# VoltageSourcePCBV3.net
KiCad netlist of a schematic drawn in EAGLE
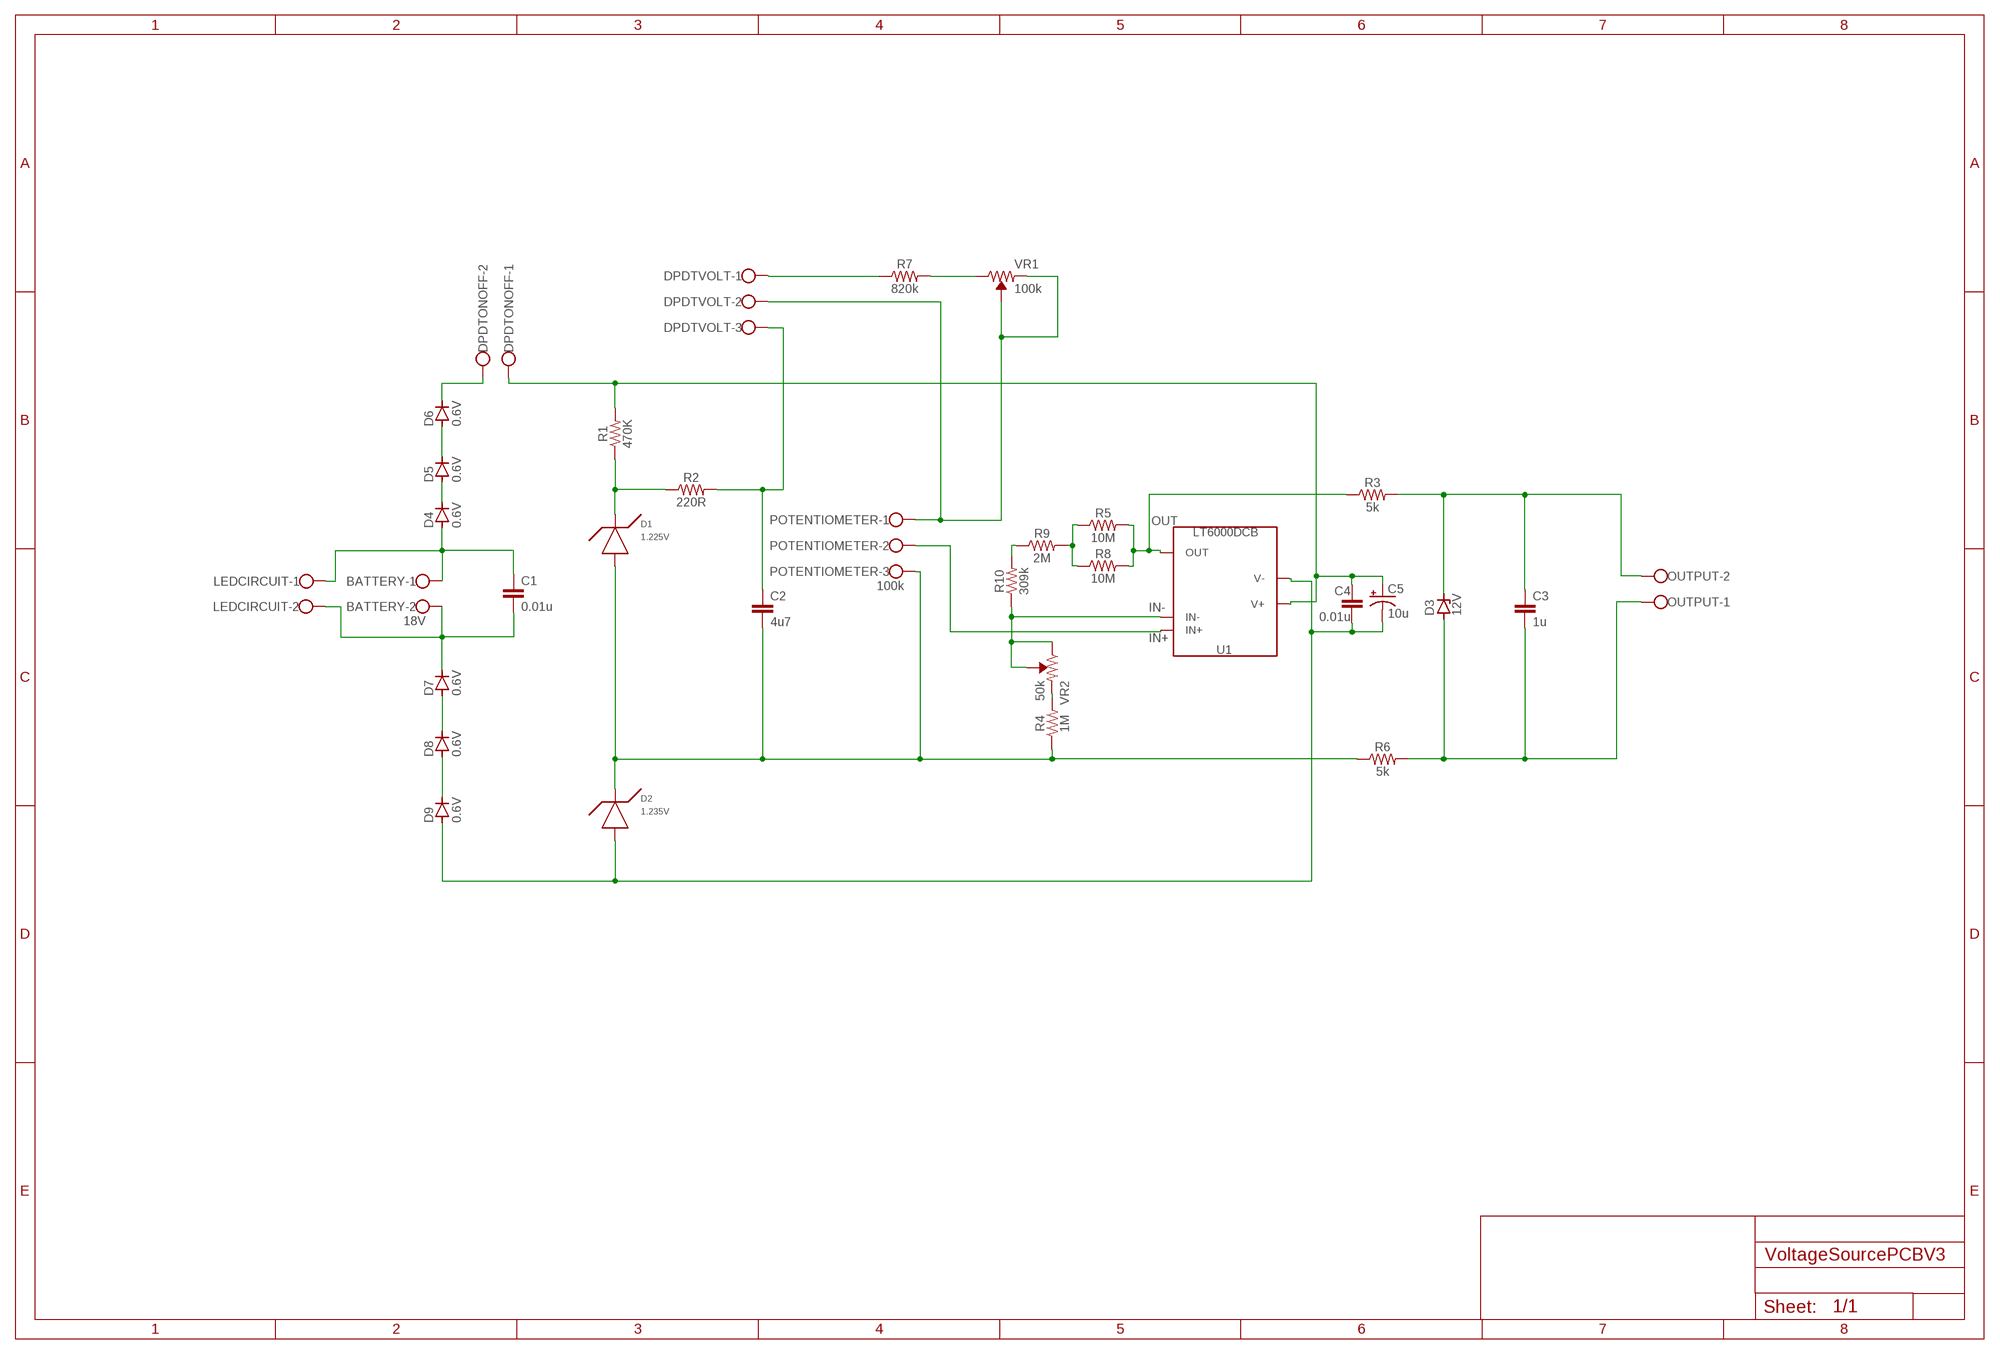
[diagram p0: schematic, sheet 1]

(export (version "E")
  (design (tool "Eeschema 10.0.6"))
  (components
    (comp (ref "BATTERY")
      (value "18V")
      (footprint "eagle-import:W237-102")
      (fields (field (name "MPN") "237-102"))
      (libsource (lib "eagle-import") (part "W237-102"))
    )
    (comp (ref "C1")
      (value "0.01u")
      (footprint "eagle-import:0805")
      (libsource (lib "eagle-import") (part "0.33UF/330NF-0805-50V-10%"))
    )
    (comp (ref "C2")
      (value "4u7")
      (footprint "eagle-import:0805")
      (libsource (lib "eagle-import") (part "0.33UF/330NF-0805-50V-10%"))
    )
    (comp (ref "C3")
      (value "1u")
      (footprint "eagle-import:0805")
      (libsource (lib "eagle-import") (part "0.33UF/330NF-0805-50V-10%"))
    )
    (comp (ref "C4")
      (value "0.01u")
      (footprint "eagle-import:0805")
      (libsource (lib "eagle-import") (part "0.33UF/330NF-0805-50V-10%"))
    )
    (comp (ref "C5")
      (value "10u")
      (footprint "eagle-import:EIA6032-NOM")
      (libsource (lib "eagle-import") (part "10UF-POLAR-EIA6032-25V-10%"))
    )
    (comp (ref "D1")
      (value "1.225V")
      (footprint "eagle-import:S8PACKAGE")
      (libsource (lib "eagle-import") (part "LT1004CS8SMD"))
    )
    (comp (ref "D2")
      (value "1.235V")
      (footprint "eagle-import:SOIC-8PACKAGE")
      (libsource (lib "eagle-import") (part "LM385BDSMD"))
    )
    (comp (ref "D3")
      (value "12V")
      (footprint "eagle-import:SOT23")
      (libsource (lib "eagle-import") (part "ZENER-DIODESOT23"))
    )
    (comp (ref "D4")
      (value "0.6V")
      (footprint "eagle-import:SOD123")
      (libsource (lib "eagle-import") (part "D-SOD123"))
    )
    (comp (ref "D5")
      (value "0.6V")
      (footprint "eagle-import:SOD123")
      (libsource (lib "eagle-import") (part "D-SOD123"))
    )
    (comp (ref "D6")
      (value "0.6V")
      (footprint "eagle-import:SOD123")
      (libsource (lib "eagle-import") (part "D-SOD123"))
    )
    (comp (ref "D7")
      (value "0.6V")
      (footprint "eagle-import:SOD123")
      (libsource (lib "eagle-import") (part "D-SOD123"))
    )
    (comp (ref "D8")
      (value "0.6V")
      (footprint "eagle-import:SOD123")
      (libsource (lib "eagle-import") (part "D-SOD123"))
    )
    (comp (ref "D9")
      (value "0.6V")
      (footprint "eagle-import:SOD123")
      (libsource (lib "eagle-import") (part "D-SOD123"))
    )
    (comp (ref "DPDTONOFF")
      (value "W237-102")
      (footprint "eagle-import:W237-102")
      (fields (field (name "MPN") "237-102"))
      (libsource (lib "eagle-import") (part "W237-102"))
    )
    (comp (ref "DPDTVOLT")
      (value "W237-103")
      (footprint "eagle-import:W237-103")
      (fields (field (name "MPN") "237-103"))
      (libsource (lib "eagle-import") (part "W237-103"))
    )
    (comp (ref "LEDCIRCUIT")
      (value "W237-102")
      (footprint "eagle-import:W237-102")
      (fields (field (name "MPN") "237-102"))
      (libsource (lib "eagle-import") (part "W237-102"))
    )
    (comp (ref "OUTPUT")
      (value "W237-102")
      (footprint "eagle-import:W237-102")
      (fields (field (name "MPN") "237-102"))
      (libsource (lib "eagle-import") (part "W237-102"))
    )
    (comp (ref "POTENTIOMETER")
      (value "100k")
      (footprint "eagle-import:W237-103")
      (fields (field (name "MPN") "237-103"))
      (libsource (lib "eagle-import") (part "W237-103"))
    )
    (comp (ref "R1")
      (value "470K")
      (footprint "eagle-import:0805")
      (libsource (lib "eagle-import") (part "RESISTOR0805"))
    )
    (comp (ref "R2")
      (value "220R")
      (footprint "eagle-import:0805")
      (libsource (lib "eagle-import") (part "RESISTOR0805"))
    )
    (comp (ref "R3")
      (value "5k")
      (footprint "eagle-import:0805")
      (libsource (lib "eagle-import") (part "RESISTOR0805"))
    )
    (comp (ref "R4")
      (value "1M")
      (footprint "eagle-import:0805")
      (libsource (lib "eagle-import") (part "RESISTOR0805"))
    )
    (comp (ref "R5")
      (value "10M")
      (footprint "eagle-import:0805")
      (libsource (lib "eagle-import") (part "RESISTOR0805"))
    )
    (comp (ref "R6")
      (value "5k")
      (footprint "eagle-import:0805")
      (libsource (lib "eagle-import") (part "RESISTOR0805"))
    )
    (comp (ref "R7")
      (value "820k")
      (footprint "eagle-import:0805")
      (libsource (lib "eagle-import") (part "RESISTOR0805"))
    )
    (comp (ref "R8")
      (value "10M")
      (footprint "eagle-import:0805")
      (libsource (lib "eagle-import") (part "RESISTOR0805"))
    )
    (comp (ref "R9")
      (value "2M")
      (footprint "eagle-import:0805")
      (libsource (lib "eagle-import") (part "RESISTOR0805"))
    )
    (comp (ref "R10")
      (value "309k")
      (footprint "eagle-import:0805")
      (libsource (lib "eagle-import") (part "RESISTOR0805"))
    )
    (comp (ref "U1")
      (value "LT6000DCB")
      (footprint "eagle-import:LT6000")
      (libsource (lib "eagle-import") (part "LT6000DCB"))
    )
    (comp (ref "VR1")
      (value "100k")
      (footprint "eagle-import:TRIMPOT-SMD-TC33X")
      (libsource (lib "eagle-import") (part "TRIMPOT-SMD-3MM-OPEN-1/10W-25%"))
    )
    (comp (ref "VR2")
      (value "50k")
      (footprint "eagle-import:TRIMPOT-SMD-TC33X")
      (libsource (lib "eagle-import") (part "TRIMPOT-SMD-3MM-OPEN-1/10W-25%"))
    )
  )
  (nets
    (net (code "1") (name "/IN+") (class "Default")
      (node (ref "POTENTIOMETER") (pin "2") (pinfunction "KL_2") (pintype "passive"))
      (node (ref "U1") (pin "3") (pinfunction "IN+_3") (pintype "input"))
    )
    (net (code "2") (name "/IN-") (class "Default")
      (node (ref "R10") (pin "1") (pinfunction "1_1") (pintype "passive"))
      (node (ref "U1") (pin "2") (pinfunction "IN-_2") (pintype "input"))
      (node (ref "VR2") (pin "1") (pinfunction "CW_1") (pintype "passive"))
      (node (ref "VR2") (pin "2") (pinfunction "WIPER_2") (pintype "passive"))
    )
    (net (code "3") (name "/OUT") (class "Default")
      (node (ref "R3") (pin "1") (pinfunction "1_1") (pintype "passive"))
      (node (ref "R5") (pin "2") (pinfunction "2_2") (pintype "passive"))
      (node (ref "R8") (pin "2") (pinfunction "2_2") (pintype "passive"))
      (node (ref "U1") (pin "4") (pinfunction "OUT_4") (pintype "output"))
    )
    (net (code "4") (name "Net-(BATTERYA-KL)") (class "Default")
      (node (ref "BATTERY") (pin "1") (pinfunction "KL_1") (pintype "passive"))
      (node (ref "C1") (pin "1") (pinfunction "1_1") (pintype "passive"))
      (node (ref "D4") (pin "2") (pinfunction "A_2") (pintype "passive"))
      (node (ref "LEDCIRCUIT") (pin "1") (pinfunction "KL_1") (pintype "passive"))
    )
    (net (code "5") (name "Net-(BATTERYB-KL)") (class "Default")
      (node (ref "BATTERY") (pin "2") (pinfunction "KL_2") (pintype "passive"))
      (node (ref "C1") (pin "2") (pinfunction "2_2") (pintype "passive"))
      (node (ref "D7") (pin "1") (pinfunction "C_1") (pintype "passive"))
      (node (ref "LEDCIRCUIT") (pin "2") (pinfunction "KL_2") (pintype "passive"))
    )
    (net (code "6") (name "Net-(C5-+)") (class "Default")
      (node (ref "C4") (pin "1") (pinfunction "1_1") (pintype "passive"))
      (node (ref "C5") (pin "A") (pinfunction "+_A") (pintype "passive"))
      (node (ref "DPDTONOFF") (pin "1") (pinfunction "KL_1") (pintype "passive"))
      (node (ref "R1") (pin "2") (pinfunction "2_2") (pintype "passive"))
      (node (ref "U1") (pin "6") (pinfunction "V+_6") (pintype "power_in"))
    )
    (net (code "7") (name "Net-(C5--)") (class "Default")
      (node (ref "C4") (pin "2") (pinfunction "2_2") (pintype "passive"))
      (node (ref "C5") (pin "C") (pinfunction "-_C") (pintype "passive"))
      (node (ref "D2") (pin "4") (pinfunction "ANODE_4") (pintype "bidirectional"))
      (node (ref "D9") (pin "2") (pinfunction "A_2") (pintype "passive"))
      (node (ref "U1") (pin "5") (pinfunction "V-_5") (pintype "power_in"))
      (node (ref "U1") (pin "7") (pinfunction "V-_7") (pintype "power_in"))
    )
    (net (code "8") (name "Net-(D1-ANODE)") (class "Default")
      (node (ref "C2") (pin "2") (pinfunction "2_2") (pintype "passive"))
      (node (ref "D1") (pin "4") (pinfunction "ANODE_4") (pintype "bidirectional"))
      (node (ref "D2") (pin "8") (pinfunction "CATHODE_8") (pintype "bidirectional"))
      (node (ref "POTENTIOMETER") (pin "3") (pinfunction "KL_3") (pintype "passive"))
      (node (ref "R4") (pin "1") (pinfunction "1_1") (pintype "passive"))
      (node (ref "R6") (pin "1") (pinfunction "1_1") (pintype "passive"))
    )
    (net (code "9") (name "Net-(D1-CATHODE-Pad6)") (class "Default")
      (node (ref "D1") (pin "6") (pinfunction "CATHODE_6") (pintype "bidirectional"))
      (node (ref "D1") (pin "8") (pinfunction "CATHODE_8") (pintype "bidirectional"))
      (node (ref "R1") (pin "1") (pinfunction "1_1") (pintype "passive"))
      (node (ref "R2") (pin "1") (pinfunction "1_1") (pintype "passive"))
    )
    (net (code "10") (name "Net-(D3-A)") (class "Default")
      (node (ref "C3") (pin "2") (pinfunction "2_2") (pintype "passive"))
      (node (ref "D3") (pin "1") (pinfunction "A_1") (pintype "passive"))
      (node (ref "OUTPUT") (pin "1") (pinfunction "KL_1") (pintype "passive"))
      (node (ref "R6") (pin "2") (pinfunction "2_2") (pintype "passive"))
    )
    (net (code "11") (name "Net-(D3-C)") (class "Default")
      (node (ref "C3") (pin "1") (pinfunction "1_1") (pintype "passive"))
      (node (ref "D3") (pin "3") (pinfunction "C_3") (pintype "passive"))
      (node (ref "OUTPUT") (pin "2") (pinfunction "KL_2") (pintype "passive"))
      (node (ref "R3") (pin "2") (pinfunction "2_2") (pintype "passive"))
    )
    (net (code "12") (name "Net-(D4-C)") (class "Default")
      (node (ref "D4") (pin "1") (pinfunction "C_1") (pintype "passive"))
      (node (ref "D5") (pin "2") (pinfunction "A_2") (pintype "passive"))
    )
    (net (code "13") (name "Net-(D5-C)") (class "Default")
      (node (ref "D5") (pin "1") (pinfunction "C_1") (pintype "passive"))
      (node (ref "D6") (pin "2") (pinfunction "A_2") (pintype "passive"))
    )
    (net (code "14") (name "Net-(D6-C)") (class "Default")
      (node (ref "D6") (pin "1") (pinfunction "C_1") (pintype "passive"))
      (node (ref "DPDTONOFF") (pin "2") (pinfunction "KL_2") (pintype "passive"))
    )
    (net (code "15") (name "Net-(D7-A)") (class "Default")
      (node (ref "D7") (pin "2") (pinfunction "A_2") (pintype "passive"))
      (node (ref "D8") (pin "1") (pinfunction "C_1") (pintype "passive"))
    )
    (net (code "16") (name "Net-(D8-A)") (class "Default")
      (node (ref "D8") (pin "2") (pinfunction "A_2") (pintype "passive"))
      (node (ref "D9") (pin "1") (pinfunction "C_1") (pintype "passive"))
    )
    (net (code "17") (name "Net-(DPDTVOLTA-KL)") (class "Default")
      (node (ref "DPDTVOLT") (pin "1") (pinfunction "KL_1") (pintype "passive"))
      (node (ref "R7") (pin "1") (pinfunction "1_1") (pintype "passive"))
    )
    (net (code "18") (name "Net-(DPDTVOLTB-KL)") (class "Default")
      (node (ref "DPDTVOLT") (pin "2") (pinfunction "KL_2") (pintype "passive"))
      (node (ref "POTENTIOMETER") (pin "1") (pinfunction "KL_1") (pintype "passive"))
      (node (ref "VR1") (pin "2") (pinfunction "WIPER_2") (pintype "passive"))
      (node (ref "VR1") (pin "3") (pinfunction "CCW_3") (pintype "passive"))
    )
    (net (code "19") (name "Net-(DPDTVOLTC-KL)") (class "Default")
      (node (ref "C2") (pin "1") (pinfunction "1_1") (pintype "passive"))
      (node (ref "DPDTVOLT") (pin "3") (pinfunction "KL_3") (pintype "passive"))
      (node (ref "R2") (pin "2") (pinfunction "2_2") (pintype "passive"))
    )
    (net (code "20") (name "Net-(R5-Pad1)") (class "Default")
      (node (ref "R5") (pin "1") (pinfunction "1_1") (pintype "passive"))
      (node (ref "R8") (pin "1") (pinfunction "1_1") (pintype "passive"))
      (node (ref "R9") (pin "2") (pinfunction "2_2") (pintype "passive"))
    )
    (net (code "21") (name "Net-(R10-Pad2)") (class "Default")
      (node (ref "R10") (pin "2") (pinfunction "2_2") (pintype "passive"))
      (node (ref "R9") (pin "1") (pinfunction "1_1") (pintype "passive"))
    )
    (net (code "22") (name "Net-(VR1-CW)") (class "Default")
      (node (ref "R7") (pin "2") (pinfunction "2_2") (pintype "passive"))
      (node (ref "VR1") (pin "1") (pinfunction "CW_1") (pintype "passive"))
    )
    (net (code "23") (name "Net-(VR2-CCW)") (class "Default")
      (node (ref "R4") (pin "2") (pinfunction "2_2") (pintype "passive"))
      (node (ref "VR2") (pin "3") (pinfunction "CCW_3") (pintype "passive"))
    )
  )
)
